# usb_breakout_rev_1.net
KiCad netlist of a schematic drawn in Altium Designer
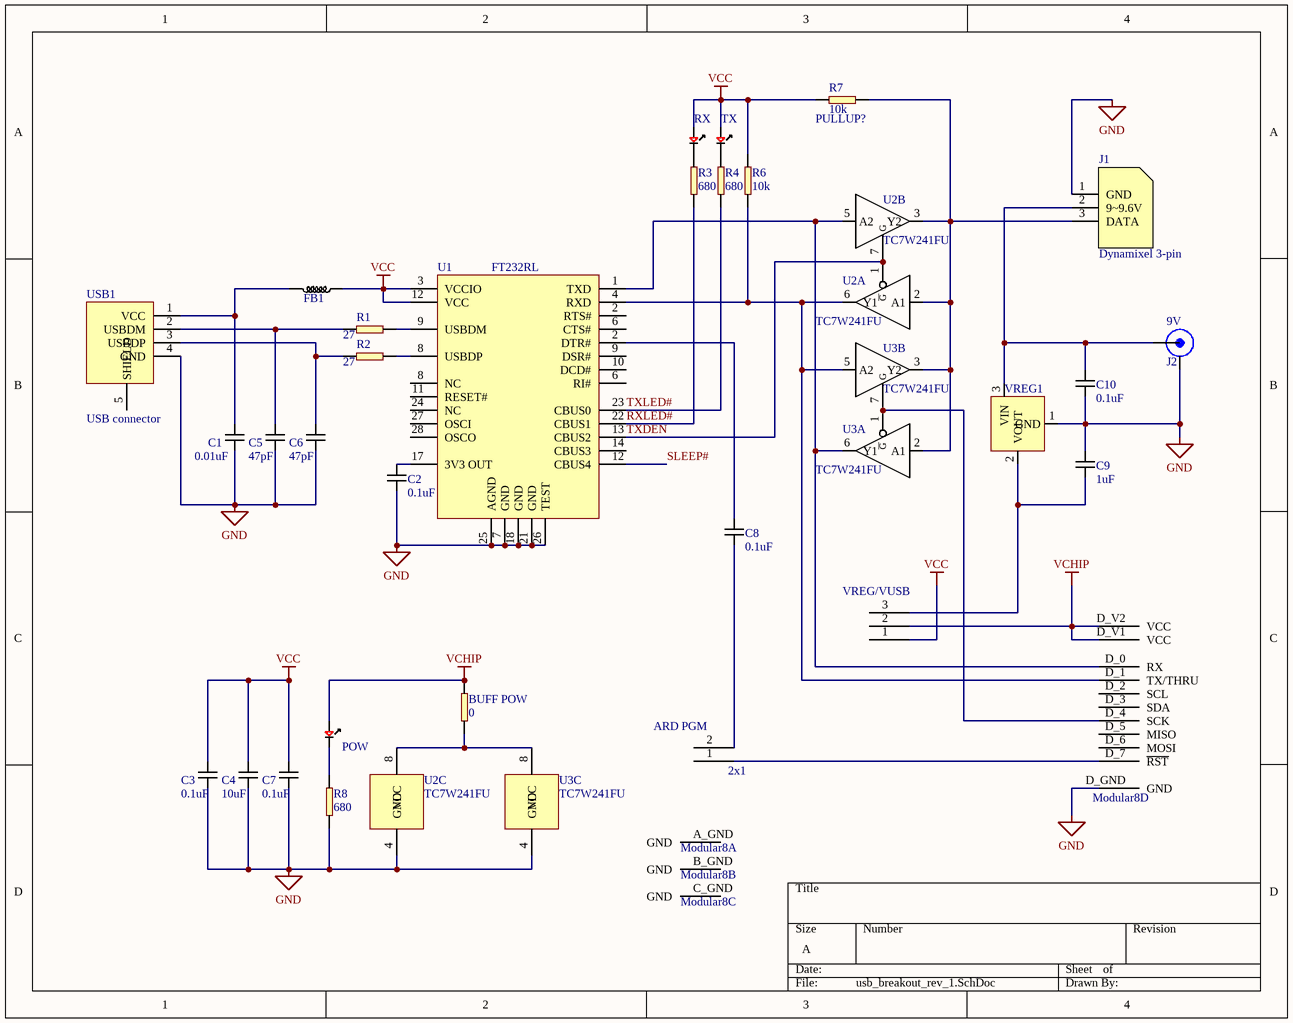
[diagram p0: usb_breakout_rev_1.SchDoc]

(export (version "E")
  (design (tool "Eeschema 10.0.6"))
  (components
    (comp (ref "ARD PGM")
      (value "2x1")
      (footprint "2x1 THRU HOLES 0.1\" PITCH")
      (libsource (lib "OpBots") (part "2x1"))
    )
    (comp (ref "BUFF POW")
      (value "R 0")
      (footprint "0603")
      (fields (field (name "R") "0"))
      (libsource (lib "RLC") (part "R 0"))
    )
    (comp (ref "C1")
      (value "C 0.01uF 25V")
      (footprint "0603")
      (fields (field (name "C") "0.01uF"))
      (libsource (lib "RLC") (part "C 0.01uF 25V"))
    )
    (comp (ref "C2")
      (value "C 0.1uF 25V")
      (footprint "0603")
      (fields (field (name "C") "0.1uF"))
      (libsource (lib "RLC") (part "C 0.1uF 25V"))
    )
    (comp (ref "C3")
      (value "C 0.1uF 25V")
      (footprint "0603")
      (fields (field (name "C") "0.1uF"))
      (libsource (lib "RLC") (part "C 0.1uF 25V"))
    )
    (comp (ref "C4")
      (value "C 10uF 25V")
      (footprint "0603")
      (fields (field (name "C") "10uF"))
      (libsource (lib "RLC") (part "C 10uF 25V"))
    )
    (comp (ref "C5")
      (value "C 47pF 50V")
      (footprint "0603")
      (fields (field (name "C") "47pF"))
      (libsource (lib "RLC") (part "C 47pF 50V"))
    )
    (comp (ref "C6")
      (value "C 47pF 50V")
      (footprint "0603")
      (fields (field (name "C") "47pF"))
      (libsource (lib "RLC") (part "C 47pF 50V"))
    )
    (comp (ref "C7")
      (value "C 0.1uF 25V")
      (footprint "0603")
      (fields (field (name "C") "0.1uF"))
      (libsource (lib "RLC") (part "C 0.1uF 25V"))
    )
    (comp (ref "C8")
      (value "C 0.1uF 25V")
      (footprint "0603")
      (fields (field (name "C") "0.1uF"))
      (libsource (lib "RLC") (part "C 0.1uF 25V"))
    )
    (comp (ref "C9")
      (value "C 1uF 25V")
      (footprint "0603")
      (fields (field (name "C") "1uF"))
      (libsource (lib "RLC") (part "C 1uF 25V"))
    )
    (comp (ref "C10")
      (value "C 0.1uF 25V")
      (footprint "0603")
      (fields (field (name "C") "0.1uF"))
      (libsource (lib "RLC") (part "C 0.1uF 25V"))
    )
    (comp (ref "FB1")
      (value "L Ferrite Bead 600ohm")
      (footprint "0603")
      (libsource (lib "RLC") (part "L Ferrite Bead 600ohm"))
    )
    (comp (ref "J1")
      (value "Dynamixel 3-pin")
      (footprint "DYNAMIXEL 3-PIN")
      (libsource (lib "OpBots") (part "Dynamixel 3-pin"))
    )
    (comp (ref "J2")
      (value "9V")
      (footprint "DC JACK 2.1MM SMT")
      (libsource (lib "OpBots") (part "SMT 2.1MM DC JACK"))
    )
    (comp (ref "Modular8")
      (value "modular8_rev2_D")
      (footprint "modular8 edge D flipped")
      (libsource (lib "OpBots") (part "modular8_rev2_D"))
    )
    (comp (ref "POW") (value "LEDG") (footprint "0805 - LED") (libsource (lib "OpBots") (part "LEDG")))
    (comp (ref "R1")
      (value "R 27")
      (footprint "0603")
      (fields (field (name "R") "27"))
      (libsource (lib "RLC") (part "R 27"))
    )
    (comp (ref "R2")
      (value "R 27")
      (footprint "0603")
      (fields (field (name "R") "27"))
      (libsource (lib "RLC") (part "R 27"))
    )
    (comp (ref "R3")
      (value "R 680")
      (footprint "0603")
      (fields (field (name "R") "680"))
      (libsource (lib "RLC") (part "R 680"))
    )
    (comp (ref "R4")
      (value "R 680")
      (footprint "0603")
      (fields (field (name "R") "680"))
      (libsource (lib "RLC") (part "R 680"))
    )
    (comp (ref "R6")
      (value "R 10k")
      (footprint "0603")
      (fields (field (name "R") "10k"))
      (libsource (lib "RLC") (part "R 10k"))
    )
    (comp (ref "R7")
      (value "PULLUP?")
      (footprint "0603")
      (fields (field (name "R") "10k"))
      (libsource (lib "") (part "R 10k_1"))
    )
    (comp (ref "R8")
      (value "R 680")
      (footprint "0603")
      (fields (field (name "R") "680"))
      (libsource (lib "RLC") (part "R 680"))
    )
    (comp (ref "RX") (value "LEDY") (footprint "0805 - LED") (libsource (lib "OpBots") (part "LEDY")))
    (comp (ref "TX") (value "LEDY") (footprint "0805 - LED") (libsource (lib "OpBots") (part "LEDY")))
    (comp (ref "U1") (value "FT232RL") (footprint "SSOP28") (libsource (lib "OpBots") (part "FT232RL")))
    (comp (ref "U2") (value "TC7W241FU") (footprint "MSOP8") (libsource (lib "") (part "TC7W241FU_1")))
    (comp (ref "U3") (value "TC7W241FU") (footprint "MSOP8") (libsource (lib "") (part "TC7W241FU_1")))
    (comp (ref "USB1")
      (value "USB connector")
      (footprint "USB MINI")
      (libsource (lib "OpBots") (part "USB connector"))
    )
    (comp (ref "VREG/VUSB")
      (value "3x1")
      (footprint "3x1 THRU HOLES 0.1\" PITCH")
      (libsource (lib "OpBots") (part "3x1"))
    )
    (comp (ref "VREG1")
      (value "MCP1754ST 5V REG")
      (footprint "SOT-23-3")
      (libsource (lib "OpBots") (part "MCP1754ST 5V REG"))
    )
  )
  (nets
    (net (code "1") (name "/RXLED#") (class "Default")
      (node (ref "R3") (pin "2") (pintype "passive"))
      (node (ref "U1") (pin "22") (pinfunction "CBUS1_22") (pintype "passive"))
    )
    (net (code "2") (name "/SLEEP#") (class "Default")
      (node (ref "U1") (pin "12") (pinfunction "CBUS4_12") (pintype "passive"))
    )
    (net (code "3") (name "/TXDEN") (class "Default")
      (node (ref "U1") (pin "13") (pinfunction "CBUS2_13") (pintype "passive"))
      (node (ref "U2") (pin "1") (pinfunction "~{G}_1") (pintype "passive"))
      (node (ref "U2") (pin "7") (pinfunction "G_7") (pintype "passive"))
    )
    (net (code "4") (name "/TXLED#") (class "Default")
      (node (ref "R4") (pin "2") (pintype "passive"))
      (node (ref "U1") (pin "23") (pinfunction "CBUS0_23") (pintype "passive"))
    )
    (net (code "5") (name "GND") (class "Default")
      (node (ref "C1") (pin "2") (pintype "passive"))
      (node (ref "C10") (pin "2") (pintype "passive"))
      (node (ref "C2") (pin "2") (pintype "passive"))
      (node (ref "C3") (pin "2") (pintype "passive"))
      (node (ref "C4") (pin "2") (pintype "passive"))
      (node (ref "C5") (pin "2") (pintype "passive"))
      (node (ref "C6") (pin "2") (pintype "passive"))
      (node (ref "C7") (pin "2") (pintype "passive"))
      (node (ref "C9") (pin "1") (pintype "passive"))
      (node (ref "J1") (pin "1") (pinfunction "GND_1") (pintype "passive"))
      (node (ref "J2") (pin "2") (pinfunction "G_2") (pintype "passive"))
      (node (ref "Modular8") (pin "D_GND") (pinfunction "GND_D_GND") (pintype "passive"))
      (node (ref "R8") (pin "2") (pintype "passive"))
      (node (ref "U1") (pin "18") (pinfunction "GND_18") (pintype "passive"))
      (node (ref "U1") (pin "21") (pinfunction "GND_21") (pintype "passive"))
      (node (ref "U1") (pin "25") (pinfunction "AGND_25") (pintype "passive"))
      (node (ref "U1") (pin "26") (pinfunction "TEST_26") (pintype "passive"))
      (node (ref "U1") (pin "7") (pinfunction "GND_7") (pintype "passive"))
      (node (ref "U2") (pin "4") (pinfunction "GND_4") (pintype "passive"))
      (node (ref "U3") (pin "4") (pinfunction "GND_4") (pintype "passive"))
      (node (ref "USB1") (pin "4") (pinfunction "GND_4") (pintype "passive"))
      (node (ref "VREG1") (pin "1") (pinfunction "GND_1") (pintype "passive"))
    )
    (net (code "6") (name "Net-(ARD PGM-Pad2)") (class "Default")
      (node (ref "ARD PGM") (pin "2") (pintype "passive"))
      (node (ref "C8") (pin "2") (pintype "passive"))
    )
    (net (code "7") (name "Net-(J1-9~9.6V)") (class "Default")
      (node (ref "C10") (pin "1") (pintype "passive"))
      (node (ref "J1") (pin "2") (pinfunction "9~9.6V_2") (pintype "passive"))
      (node (ref "J2") (pin "1") (pinfunction "S_1") (pintype "passive"))
      (node (ref "VREG1") (pin "3") (pinfunction "VIN_3") (pintype "passive"))
    )
    (net (code "8") (name "Net-(J1-DATA)") (class "Default")
      (node (ref "J1") (pin "3") (pinfunction "DATA_3") (pintype "passive"))
      (node (ref "R7") (pin "2") (pintype "passive"))
      (node (ref "U2") (pin "2") (pinfunction "A1_2") (pintype "passive"))
      (node (ref "U2") (pin "3") (pinfunction "Y2_3") (pintype "passive"))
      (node (ref "U3") (pin "2") (pinfunction "A1_2") (pintype "passive"))
      (node (ref "U3") (pin "3") (pinfunction "Y2_3") (pintype "passive"))
    )
    (net (code "9") (name "Net-(Modular8D-RX)") (class "Default")
      (node (ref "Modular8") (pin "D_0") (pinfunction "RX_D_0") (pintype "passive"))
      (node (ref "U1") (pin "1") (pinfunction "TXD_1") (pintype "passive"))
      (node (ref "U2") (pin "5") (pinfunction "A2_5") (pintype "passive"))
      (node (ref "U3") (pin "6") (pinfunction "Y1_6") (pintype "passive"))
    )
    (net (code "10") (name "Net-(Modular8D-SCK)") (class "Default")
      (node (ref "Modular8") (pin "D_4") (pinfunction "SCK_D_4") (pintype "passive"))
      (node (ref "U3") (pin "1") (pinfunction "~{G}_1") (pintype "passive"))
      (node (ref "U3") (pin "7") (pinfunction "G_7") (pintype "passive"))
    )
    (net (code "11") (name "Net-(Modular8D-TX{slash}THRU)") (class "Default")
      (node (ref "Modular8") (pin "D_1") (pinfunction "TX/THRU_D_1") (pintype "passive"))
      (node (ref "R6") (pin "2") (pintype "passive"))
      (node (ref "U1") (pin "4") (pinfunction "RXD_4") (pintype "passive"))
      (node (ref "U2") (pin "6") (pinfunction "Y1_6") (pintype "passive"))
      (node (ref "U3") (pin "5") (pinfunction "A2_5") (pintype "passive"))
    )
    (net (code "12") (name "Net-(Modular8D-~{RST})") (class "Default")
      (node (ref "ARD PGM") (pin "1") (pintype "passive"))
      (node (ref "Modular8") (pin "D_7") (pinfunction "~{RST}_D_7") (pintype "passive"))
    )
    (net (code "13") (name "Net-(POW-K)") (class "Default")
      (node (ref "POW") (pin "2") (pinfunction "K_2") (pintype "passive"))
      (node (ref "R8") (pin "1") (pintype "passive"))
    )
    (net (code "14") (name "Net-(RX-K)") (class "Default")
      (node (ref "R3") (pin "1") (pintype "passive"))
      (node (ref "RX") (pin "2") (pinfunction "K_2") (pintype "passive"))
    )
    (net (code "15") (name "Net-(TX-K)") (class "Default")
      (node (ref "R4") (pin "1") (pintype "passive"))
      (node (ref "TX") (pin "2") (pinfunction "K_2") (pintype "passive"))
    )
    (net (code "16") (name "Net-(U1-3V3_OUT)") (class "Default")
      (node (ref "C2") (pin "1") (pintype "passive"))
      (node (ref "U1") (pin "17") (pinfunction "3V3_OUT_17") (pintype "passive"))
    )
    (net (code "17") (name "Net-(U1-DTR#)") (class "Default")
      (node (ref "C8") (pin "1") (pintype "passive"))
      (node (ref "U1") (pin "2") (pinfunction "DTR#_2") (pintype "passive"))
    )
    (net (code "18") (name "Net-(U1-USBDM)") (class "Default")
      (node (ref "R1") (pin "2") (pintype "passive"))
      (node (ref "U1") (pin "9") (pinfunction "USBDM_9") (pintype "passive"))
    )
    (net (code "19") (name "Net-(U1-USBDP)") (class "Default")
      (node (ref "R2") (pin "2") (pintype "passive"))
      (node (ref "U1") (pin "8") (pinfunction "USBDP_8") (pintype "passive"))
    )
    (net (code "20") (name "Net-(U2C-VCC)") (class "Default")
      (node (ref "BUFF POW") (pin "2") (pintype "passive"))
      (node (ref "U2") (pin "8") (pinfunction "VCC_8") (pintype "passive"))
      (node (ref "U3") (pin "8") (pinfunction "VCC_8") (pintype "passive"))
    )
    (net (code "21") (name "Net-(USB1-USBDM)") (class "Default")
      (node (ref "C5") (pin "1") (pintype "passive"))
      (node (ref "R1") (pin "1") (pintype "passive"))
      (node (ref "USB1") (pin "2") (pinfunction "USBDM_2") (pintype "passive"))
    )
    (net (code "22") (name "Net-(USB1-USBDP)") (class "Default")
      (node (ref "C6") (pin "1") (pintype "passive"))
      (node (ref "R2") (pin "1") (pintype "passive"))
      (node (ref "USB1") (pin "3") (pinfunction "USBDP_3") (pintype "passive"))
    )
    (net (code "23") (name "Net-(USB1-VCC)") (class "Default")
      (node (ref "C1") (pin "1") (pintype "passive"))
      (node (ref "FB1") (pin "1") (pintype "passive"))
      (node (ref "USB1") (pin "1") (pinfunction "VCC_1") (pintype "passive"))
    )
    (net (code "24") (name "Net-(VREG1-VOUT)") (class "Default")
      (node (ref "C9") (pin "2") (pintype "passive"))
      (node (ref "VREG/VUSB") (pin "3") (pintype "passive"))
      (node (ref "VREG1") (pin "2") (pinfunction "VOUT_2") (pintype "passive"))
    )
    (net (code "25") (name "VCC") (class "Default")
      (node (ref "C3") (pin "1") (pintype "passive"))
      (node (ref "C4") (pin "1") (pintype "passive"))
      (node (ref "C7") (pin "1") (pintype "passive"))
      (node (ref "FB1") (pin "2") (pintype "passive"))
      (node (ref "R6") (pin "1") (pintype "passive"))
      (node (ref "R7") (pin "1") (pintype "passive"))
      (node (ref "RX") (pin "1") (pinfunction "A_1") (pintype "passive"))
      (node (ref "TX") (pin "1") (pinfunction "A_1") (pintype "passive"))
      (node (ref "U1") (pin "12") (pinfunction "VCC_12") (pintype "passive"))
      (node (ref "U1") (pin "3") (pinfunction "VCCIO_3") (pintype "passive"))
      (node (ref "VREG/VUSB") (pin "1") (pintype "passive"))
    )
    (net (code "26") (name "VCHIP") (class "Default")
      (node (ref "BUFF POW") (pin "1") (pintype "passive"))
      (node (ref "Modular8") (pin "D_V1") (pinfunction "VCC_D_V1") (pintype "passive"))
      (node (ref "Modular8") (pin "D_V2") (pinfunction "VCC_D_V2") (pintype "passive"))
      (node (ref "POW") (pin "1") (pinfunction "A_1") (pintype "passive"))
      (node (ref "VREG/VUSB") (pin "2") (pintype "passive"))
    )
    (net (code "27") (name "unconnected-(Modular8A-GND-PadA_GND)") (class "Default")
      (node (ref "Modular8") (pin "A_GND") (pinfunction "GND_A_GND") (pintype "passive"))
    )
    (net (code "28") (name "unconnected-(Modular8B-GND-PadB_GND)") (class "Default")
      (node (ref "Modular8") (pin "B_GND") (pinfunction "GND_B_GND") (pintype "passive"))
    )
    (net (code "29") (name "unconnected-(Modular8C-GND-PadC_GND)") (class "Default")
      (node (ref "Modular8") (pin "C_GND") (pinfunction "GND_C_GND") (pintype "passive"))
    )
    (net (code "30") (name "unconnected-(Modular8D-MISO-PadD_5)") (class "Default")
      (node (ref "Modular8") (pin "D_5") (pinfunction "MISO_D_5") (pintype "passive"))
    )
    (net (code "31") (name "unconnected-(Modular8D-MOSI-PadD_6)") (class "Default")
      (node (ref "Modular8") (pin "D_6") (pinfunction "MOSI_D_6") (pintype "passive"))
    )
    (net (code "32") (name "unconnected-(Modular8D-SCL-PadD_2)") (class "Default")
      (node (ref "Modular8") (pin "D_2") (pinfunction "SCL_D_2") (pintype "passive"))
    )
    (net (code "33") (name "unconnected-(Modular8D-SDA-PadD_3)") (class "Default")
      (node (ref "Modular8") (pin "D_3") (pinfunction "SDA_D_3") (pintype "passive"))
    )
    (net (code "34") (name "unconnected-(U1-CBUS3-Pad14)") (class "Default")
      (node (ref "U1") (pin "14") (pinfunction "CBUS3_14") (pintype "passive"))
    )
    (net (code "35") (name "unconnected-(U1-CTS#-Pad6)") (class "Default")
      (node (ref "U1") (pin "6") (pinfunction "CTS#_6") (pintype "passive"))
    )
    (net (code "36") (name "unconnected-(U1-DCD#-Pad10)") (class "Default")
      (node (ref "U1") (pin "10") (pinfunction "DCD#_10") (pintype "passive"))
    )
    (net (code "37") (name "unconnected-(U1-DSR#-Pad9)") (class "Default")
      (node (ref "U1") (pin "9") (pinfunction "DSR#_9") (pintype "passive"))
    )
    (net (code "38") (name "unconnected-(U1-NC-Pad8)") (class "Default")
      (node (ref "U1") (pin "8") (pinfunction "NC_8") (pintype "passive"))
    )
    (net (code "39") (name "unconnected-(U1-NC-Pad24)") (class "Default")
      (node (ref "U1") (pin "24") (pinfunction "NC_24") (pintype "passive"))
    )
    (net (code "40") (name "unconnected-(U1-OSCI-Pad27)") (class "Default")
      (node (ref "U1") (pin "27") (pinfunction "OSCI_27") (pintype "passive"))
    )
    (net (code "41") (name "unconnected-(U1-OSCO-Pad28)") (class "Default")
      (node (ref "U1") (pin "28") (pinfunction "OSCO_28") (pintype "passive"))
    )
    (net (code "42") (name "unconnected-(U1-RESET#-Pad11)") (class "Default")
      (node (ref "U1") (pin "11") (pinfunction "RESET#_11") (pintype "passive"))
    )
    (net (code "43") (name "unconnected-(U1-RI#-Pad6)") (class "Default")
      (node (ref "U1") (pin "6") (pinfunction "RI#_6") (pintype "passive"))
    )
    (net (code "44") (name "unconnected-(U1-RTS#-Pad2)") (class "Default")
      (node (ref "U1") (pin "2") (pinfunction "RTS#_2") (pintype "passive"))
    )
    (net (code "45") (name "unconnected-(USB1-SHIELD-Pad5)") (class "Default")
      (node (ref "USB1") (pin "5") (pinfunction "SHIELD_5") (pintype "passive"))
    )
  )
)
